# Mainboard.net
KiCad netlist of a schematic drawn in EAGLE
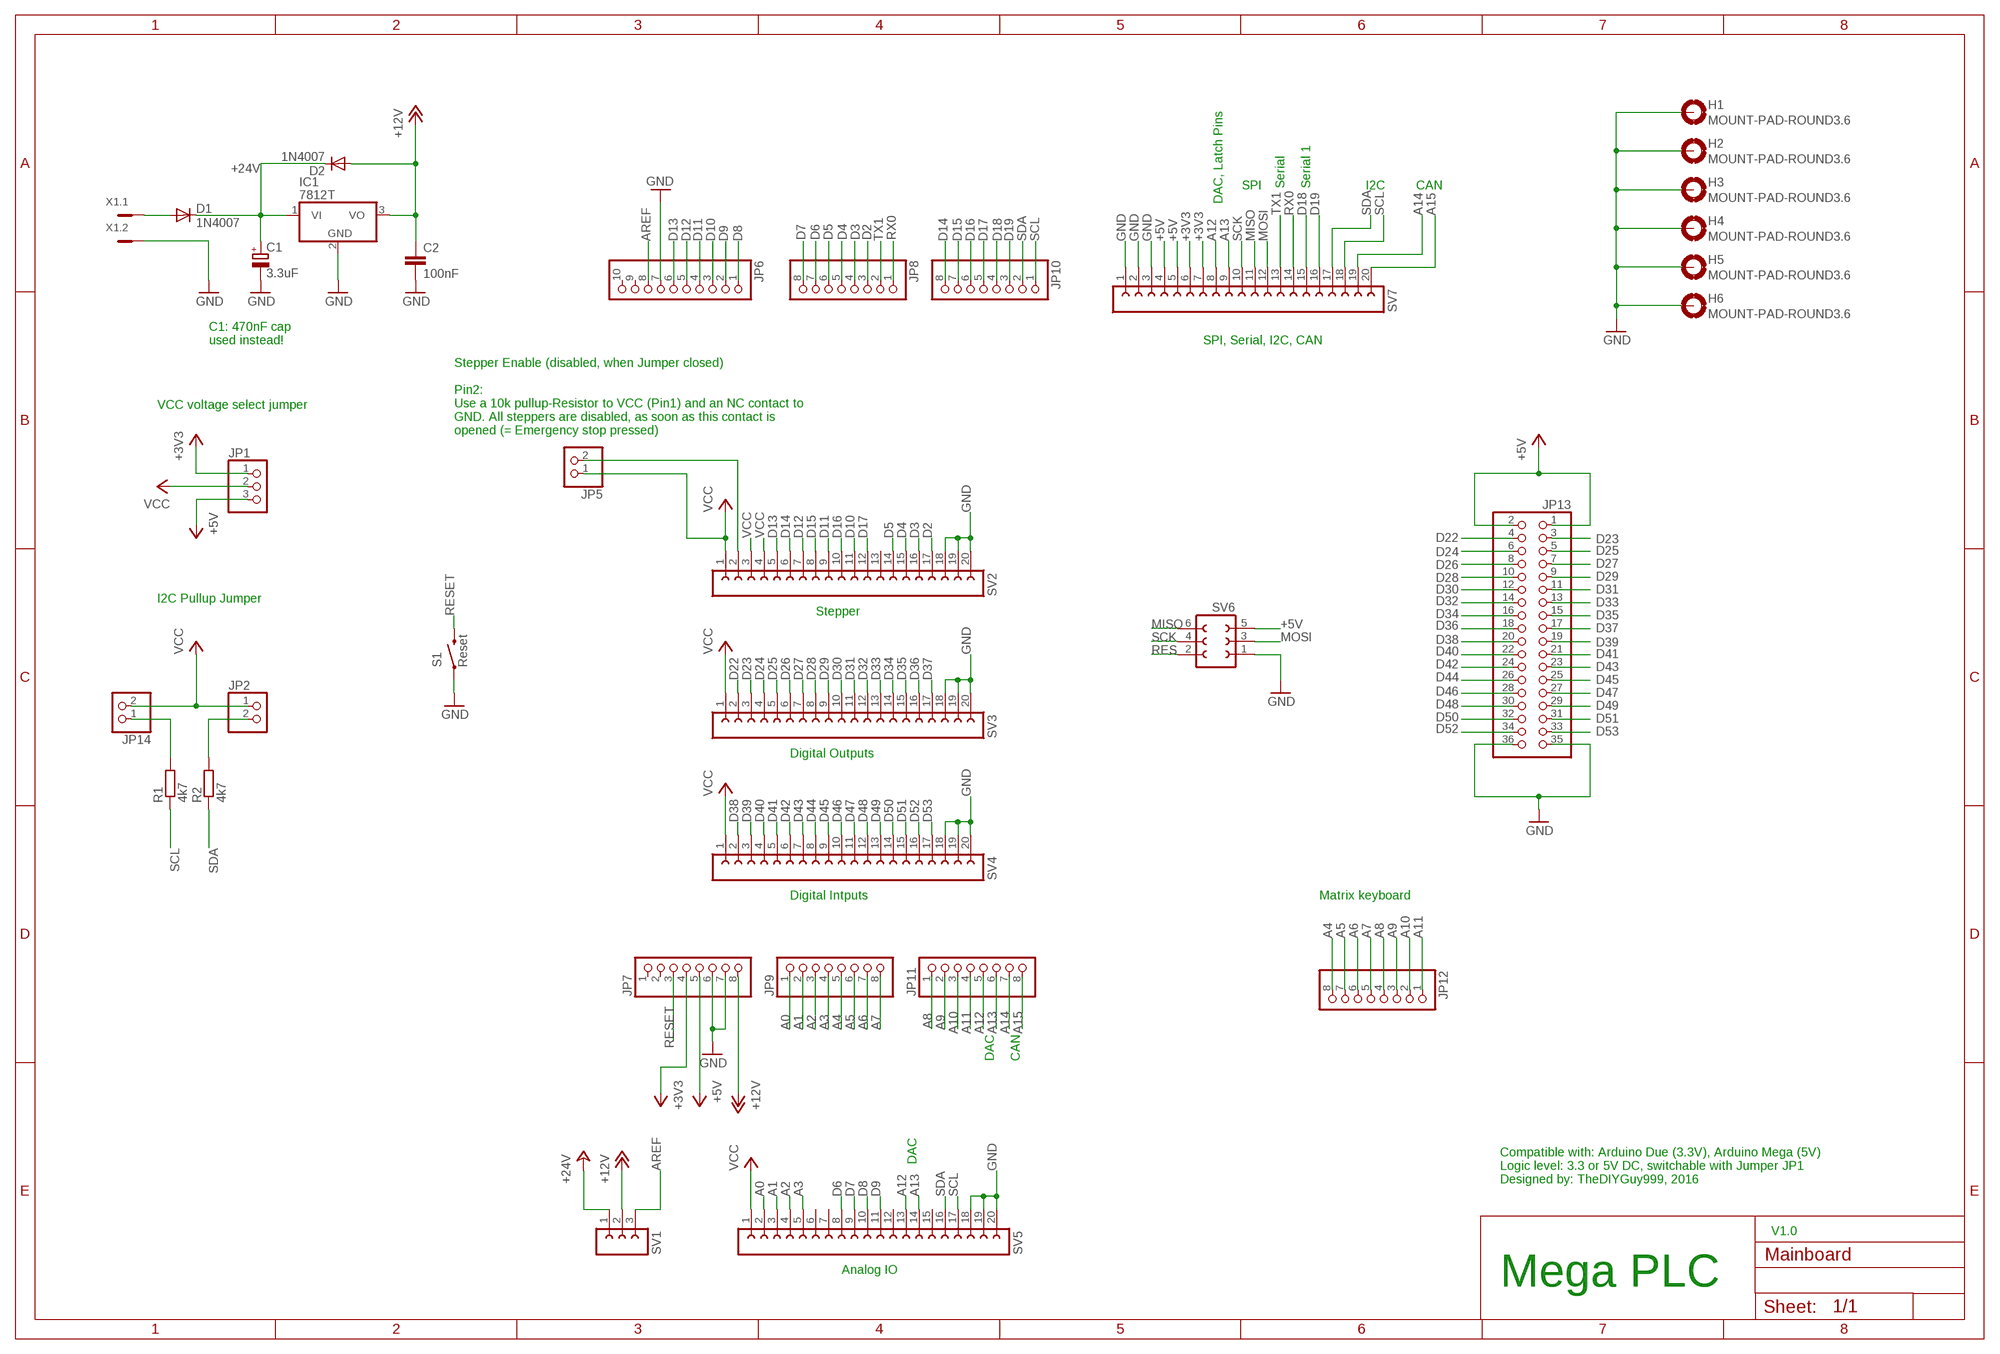
[diagram p0: schematic, sheet 1]

(export (version "E")
  (design (tool "Eeschema 10.0.6"))
  (components
    (comp (ref "C1")
      (value "3.3uF")
      (footprint "eagle-import:B45181A")
      (libsource (lib "eagle-import") (part "CPOL-EUB45181A"))
    )
    (comp (ref "C2")
      (value "100nF")
      (footprint "eagle-import:C025-024X044")
      (libsource (lib "eagle-import") (part "C-EU025-024X044"))
    )
    (comp (ref "D1")
      (value "1N4007")
      (footprint "eagle-import:DO41-10")
      (libsource (lib "eagle-import") (part "1N4004"))
    )
    (comp (ref "D2")
      (value "1N4007")
      (footprint "eagle-import:DO41-10")
      (libsource (lib "eagle-import") (part "1N4004"))
    )
    (comp (ref "H1")
      (value "MOUNT-PAD-ROUND3.6")
      (footprint "eagle-import:3,6-PAD")
      (libsource (lib "eagle-import") (part "MOUNT-PAD-ROUND3.6"))
    )
    (comp (ref "H2")
      (value "MOUNT-PAD-ROUND3.6")
      (footprint "eagle-import:3,6-PAD")
      (libsource (lib "eagle-import") (part "MOUNT-PAD-ROUND3.6"))
    )
    (comp (ref "H3")
      (value "MOUNT-PAD-ROUND3.6")
      (footprint "eagle-import:3,6-PAD")
      (libsource (lib "eagle-import") (part "MOUNT-PAD-ROUND3.6"))
    )
    (comp (ref "H4")
      (value "MOUNT-PAD-ROUND3.6")
      (footprint "eagle-import:3,6-PAD")
      (libsource (lib "eagle-import") (part "MOUNT-PAD-ROUND3.6"))
    )
    (comp (ref "H5")
      (value "MOUNT-PAD-ROUND3.6")
      (footprint "eagle-import:3,6-PAD")
      (libsource (lib "eagle-import") (part "MOUNT-PAD-ROUND3.6"))
    )
    (comp (ref "H6")
      (value "MOUNT-PAD-ROUND3.6")
      (footprint "eagle-import:3,6-PAD")
      (libsource (lib "eagle-import") (part "MOUNT-PAD-ROUND3.6"))
    )
    (comp (ref "IC1")
      (value "7812T")
      (footprint "eagle-import:TO220H")
      (libsource (lib "eagle-import") (part "78T12"))
    )
    (comp (ref "JP1")
      (value "PINHD-1X3")
      (footprint "eagle-import:1X03")
      (libsource (lib "eagle-import") (part "PINHD-1X3"))
    )
    (comp (ref "JP2")
      (value "PINHD-1X2")
      (footprint "eagle-import:1X02")
      (libsource (lib "eagle-import") (part "PINHD-1X2"))
    )
    (comp (ref "JP5")
      (value "PINHD-1X2")
      (footprint "eagle-import:1X02")
      (libsource (lib "eagle-import") (part "PINHD-1X2"))
    )
    (comp (ref "JP6")
      (value "PINHD-1X10")
      (footprint "eagle-import:1X10")
      (libsource (lib "eagle-import") (part "PINHD-1X10"))
    )
    (comp (ref "JP7")
      (value "PINHD-1X8")
      (footprint "eagle-import:1X08")
      (libsource (lib "eagle-import") (part "PINHD-1X8"))
    )
    (comp (ref "JP8")
      (value "PINHD-1X8")
      (footprint "eagle-import:1X08")
      (libsource (lib "eagle-import") (part "PINHD-1X8"))
    )
    (comp (ref "JP9")
      (value "PINHD-1X8")
      (footprint "eagle-import:1X08")
      (libsource (lib "eagle-import") (part "PINHD-1X8"))
    )
    (comp (ref "JP10")
      (value "PINHD-1X8")
      (footprint "eagle-import:1X08")
      (libsource (lib "eagle-import") (part "PINHD-1X8"))
    )
    (comp (ref "JP11")
      (value "PINHD-1X8")
      (footprint "eagle-import:1X08")
      (libsource (lib "eagle-import") (part "PINHD-1X8"))
    )
    (comp (ref "JP12")
      (value "PINHD-1X8")
      (footprint "eagle-import:1X08")
      (libsource (lib "eagle-import") (part "PINHD-1X8"))
    )
    (comp (ref "JP13")
      (value "PINHD-2X18")
      (footprint "eagle-import:2X18")
      (libsource (lib "eagle-import") (part "PINHD-2X18"))
    )
    (comp (ref "JP14")
      (value "PINHD-1X2")
      (footprint "eagle-import:1X02")
      (libsource (lib "eagle-import") (part "PINHD-1X2"))
    )
    (comp (ref "R1")
      (value "4k7")
      (footprint "eagle-import:0207_10")
      (libsource (lib "eagle-import") (part "R-EU_0207/10"))
    )
    (comp (ref "R2")
      (value "4k7")
      (footprint "eagle-import:0207_10")
      (libsource (lib "eagle-import") (part "R-EU_0207/10"))
    )
    (comp (ref "S1")
      (value "Reset")
      (footprint "eagle-import:TACTILE-PTH")
      (libsource (lib "eagle-import") (part "SWITCH-MOMENTARY-2PTH"))
    )
    (comp (ref "SV1")
      (value "FE03-1")
      (footprint "eagle-import:FE03-1")
      (libsource (lib "eagle-import") (part "FE03-1"))
    )
    (comp (ref "SV2")
      (value "FE20-1")
      (footprint "eagle-import:FE20")
      (libsource (lib "eagle-import") (part "FE20-1"))
    )
    (comp (ref "SV3")
      (value "FE20-1")
      (footprint "eagle-import:FE20")
      (libsource (lib "eagle-import") (part "FE20-1"))
    )
    (comp (ref "SV4")
      (value "FE20-1")
      (footprint "eagle-import:FE20")
      (libsource (lib "eagle-import") (part "FE20-1"))
    )
    (comp (ref "SV5")
      (value "FE20-1")
      (footprint "eagle-import:FE20")
      (libsource (lib "eagle-import") (part "FE20-1"))
    )
    (comp (ref "SV6")
      (value "FE03-2")
      (footprint "eagle-import:FE03-2")
      (libsource (lib "eagle-import") (part "FE03-2"))
    )
    (comp (ref "SV7")
      (value "FE20-1")
      (footprint "eagle-import:FE20")
      (libsource (lib "eagle-import") (part "FE20-1"))
    )
    (comp (ref "X1")
      (value "MC2")
      (footprint "eagle-import:MC2")
      (libsource (lib "eagle-import") (part "MC2"))
    )
  )
  (nets
    (net (code "1") (name "+3V3") (class "Default")
      (node (ref "JP1") (pin "1") (pinfunction "1_1") (pintype "passive"))
      (node (ref "JP7") (pin "4") (pinfunction "4_4") (pintype "passive"))
      (node (ref "SV7") (pin "6") (pinfunction "6_6") (pintype "passive"))
      (node (ref "SV7") (pin "7") (pinfunction "7_7") (pintype "passive"))
    )
    (net (code "2") (name "+5V") (class "Default")
      (node (ref "JP1") (pin "3") (pinfunction "3_3") (pintype "passive"))
      (node (ref "JP13") (pin "1") (pinfunction "1_1") (pintype "passive"))
      (node (ref "JP13") (pin "2") (pinfunction "2_2") (pintype "passive"))
      (node (ref "JP7") (pin "5") (pinfunction "5_5") (pintype "passive"))
      (node (ref "SV6") (pin "5") (pinfunction "5_5") (pintype "passive"))
      (node (ref "SV7") (pin "4") (pinfunction "4_4") (pintype "passive"))
      (node (ref "SV7") (pin "5") (pinfunction "5_5") (pintype "passive"))
    )
    (net (code "3") (name "+12V") (class "Default")
      (node (ref "C2") (pin "1") (pinfunction "1_1") (pintype "passive"))
      (node (ref "D2") (pin "A") (pinfunction "A_A") (pintype "passive"))
      (node (ref "IC1") (pin "3") (pinfunction "VO_3") (pintype "passive"))
      (node (ref "JP7") (pin "8") (pinfunction "8_8") (pintype "passive"))
      (node (ref "SV1") (pin "2") (pinfunction "2_2") (pintype "passive"))
    )
    (net (code "4") (name "+24V") (class "Default")
      (node (ref "C1") (pin "+") (pinfunction "+_+") (pintype "passive"))
      (node (ref "D1") (pin "C") (pinfunction "C_C") (pintype "passive"))
      (node (ref "D2") (pin "C") (pinfunction "C_C") (pintype "passive"))
      (node (ref "IC1") (pin "1") (pinfunction "VI_1") (pintype "input"))
      (node (ref "SV1") (pin "1") (pinfunction "1_1") (pintype "passive"))
    )
    (net (code "5") (name "/A0") (class "Default")
      (node (ref "JP9") (pin "1") (pinfunction "1_1") (pintype "passive"))
      (node (ref "SV5") (pin "2") (pinfunction "2_2") (pintype "passive"))
    )
    (net (code "6") (name "/A1") (class "Default")
      (node (ref "JP9") (pin "2") (pinfunction "2_2") (pintype "passive"))
      (node (ref "SV5") (pin "3") (pinfunction "3_3") (pintype "passive"))
    )
    (net (code "7") (name "/A2") (class "Default")
      (node (ref "JP9") (pin "3") (pinfunction "3_3") (pintype "passive"))
      (node (ref "SV5") (pin "4") (pinfunction "4_4") (pintype "passive"))
    )
    (net (code "8") (name "/A3") (class "Default")
      (node (ref "JP9") (pin "4") (pinfunction "4_4") (pintype "passive"))
      (node (ref "SV5") (pin "5") (pinfunction "5_5") (pintype "passive"))
    )
    (net (code "9") (name "/A4") (class "Default")
      (node (ref "JP12") (pin "8") (pinfunction "8_8") (pintype "passive"))
      (node (ref "JP9") (pin "5") (pinfunction "5_5") (pintype "passive"))
    )
    (net (code "10") (name "/A5") (class "Default")
      (node (ref "JP12") (pin "7") (pinfunction "7_7") (pintype "passive"))
      (node (ref "JP9") (pin "6") (pinfunction "6_6") (pintype "passive"))
    )
    (net (code "11") (name "/A6") (class "Default")
      (node (ref "JP12") (pin "6") (pinfunction "6_6") (pintype "passive"))
      (node (ref "JP9") (pin "7") (pinfunction "7_7") (pintype "passive"))
    )
    (net (code "12") (name "/A7") (class "Default")
      (node (ref "JP12") (pin "5") (pinfunction "5_5") (pintype "passive"))
      (node (ref "JP9") (pin "8") (pinfunction "8_8") (pintype "passive"))
    )
    (net (code "13") (name "/A8") (class "Default")
      (node (ref "JP11") (pin "1") (pinfunction "1_1") (pintype "passive"))
      (node (ref "JP12") (pin "4") (pinfunction "4_4") (pintype "passive"))
    )
    (net (code "14") (name "/A9") (class "Default")
      (node (ref "JP11") (pin "2") (pinfunction "2_2") (pintype "passive"))
      (node (ref "JP12") (pin "3") (pinfunction "3_3") (pintype "passive"))
    )
    (net (code "15") (name "/A10") (class "Default")
      (node (ref "JP11") (pin "3") (pinfunction "3_3") (pintype "passive"))
      (node (ref "JP12") (pin "2") (pinfunction "2_2") (pintype "passive"))
    )
    (net (code "16") (name "/A11") (class "Default")
      (node (ref "JP11") (pin "4") (pinfunction "4_4") (pintype "passive"))
      (node (ref "JP12") (pin "1") (pinfunction "1_1") (pintype "passive"))
    )
    (net (code "17") (name "/A12") (class "Default")
      (node (ref "JP11") (pin "5") (pinfunction "5_5") (pintype "passive"))
      (node (ref "SV5") (pin "13") (pinfunction "13_13") (pintype "passive"))
      (node (ref "SV7") (pin "8") (pinfunction "8_8") (pintype "passive"))
    )
    (net (code "18") (name "/A13") (class "Default")
      (node (ref "JP11") (pin "6") (pinfunction "6_6") (pintype "passive"))
      (node (ref "SV5") (pin "14") (pinfunction "14_14") (pintype "passive"))
      (node (ref "SV7") (pin "9") (pinfunction "9_9") (pintype "passive"))
    )
    (net (code "19") (name "/A14") (class "Default")
      (node (ref "JP11") (pin "7") (pinfunction "7_7") (pintype "passive"))
      (node (ref "SV7") (pin "19") (pinfunction "19_19") (pintype "passive"))
    )
    (net (code "20") (name "/A15") (class "Default")
      (node (ref "JP11") (pin "8") (pinfunction "8_8") (pintype "passive"))
      (node (ref "SV7") (pin "20") (pinfunction "20_20") (pintype "passive"))
    )
    (net (code "21") (name "/AREF") (class "Default")
      (node (ref "JP6") (pin "8") (pinfunction "8_8") (pintype "passive"))
      (node (ref "SV1") (pin "3") (pinfunction "3_3") (pintype "passive"))
    )
    (net (code "22") (name "/D2") (class "Default")
      (node (ref "JP8") (pin "3") (pinfunction "3_3") (pintype "passive"))
      (node (ref "SV2") (pin "17") (pinfunction "17_17") (pintype "passive"))
    )
    (net (code "23") (name "/D3") (class "Default")
      (node (ref "JP8") (pin "4") (pinfunction "4_4") (pintype "passive"))
      (node (ref "SV2") (pin "16") (pinfunction "16_16") (pintype "passive"))
    )
    (net (code "24") (name "/D4") (class "Default")
      (node (ref "JP8") (pin "5") (pinfunction "5_5") (pintype "passive"))
      (node (ref "SV2") (pin "15") (pinfunction "15_15") (pintype "passive"))
    )
    (net (code "25") (name "/D5") (class "Default")
      (node (ref "JP8") (pin "6") (pinfunction "6_6") (pintype "passive"))
      (node (ref "SV2") (pin "14") (pinfunction "14_14") (pintype "passive"))
    )
    (net (code "26") (name "/D6") (class "Default")
      (node (ref "JP8") (pin "7") (pinfunction "7_7") (pintype "passive"))
      (node (ref "SV5") (pin "8") (pinfunction "8_8") (pintype "passive"))
    )
    (net (code "27") (name "/D7") (class "Default")
      (node (ref "JP8") (pin "8") (pinfunction "8_8") (pintype "passive"))
      (node (ref "SV5") (pin "9") (pinfunction "9_9") (pintype "passive"))
    )
    (net (code "28") (name "/D8") (class "Default")
      (node (ref "JP6") (pin "1") (pinfunction "1_1") (pintype "passive"))
      (node (ref "SV5") (pin "10") (pinfunction "10_10") (pintype "passive"))
    )
    (net (code "29") (name "/D9") (class "Default")
      (node (ref "JP6") (pin "2") (pinfunction "2_2") (pintype "passive"))
      (node (ref "SV5") (pin "11") (pinfunction "11_11") (pintype "passive"))
    )
    (net (code "30") (name "/D10") (class "Default")
      (node (ref "JP6") (pin "3") (pinfunction "3_3") (pintype "passive"))
      (node (ref "SV2") (pin "11") (pinfunction "11_11") (pintype "passive"))
    )
    (net (code "31") (name "/D11") (class "Default")
      (node (ref "JP6") (pin "4") (pinfunction "4_4") (pintype "passive"))
      (node (ref "SV2") (pin "9") (pinfunction "9_9") (pintype "passive"))
    )
    (net (code "32") (name "/D12") (class "Default")
      (node (ref "JP6") (pin "5") (pinfunction "5_5") (pintype "passive"))
      (node (ref "SV2") (pin "7") (pinfunction "7_7") (pintype "passive"))
    )
    (net (code "33") (name "/D13") (class "Default")
      (node (ref "JP6") (pin "6") (pinfunction "6_6") (pintype "passive"))
      (node (ref "SV2") (pin "5") (pinfunction "5_5") (pintype "passive"))
    )
    (net (code "34") (name "/D14") (class "Default")
      (node (ref "JP10") (pin "8") (pinfunction "8_8") (pintype "passive"))
      (node (ref "SV2") (pin "6") (pinfunction "6_6") (pintype "passive"))
    )
    (net (code "35") (name "/D15") (class "Default")
      (node (ref "JP10") (pin "7") (pinfunction "7_7") (pintype "passive"))
      (node (ref "SV2") (pin "8") (pinfunction "8_8") (pintype "passive"))
    )
    (net (code "36") (name "/D16") (class "Default")
      (node (ref "JP10") (pin "6") (pinfunction "6_6") (pintype "passive"))
      (node (ref "SV2") (pin "10") (pinfunction "10_10") (pintype "passive"))
    )
    (net (code "37") (name "/D17") (class "Default")
      (node (ref "JP10") (pin "5") (pinfunction "5_5") (pintype "passive"))
      (node (ref "SV2") (pin "12") (pinfunction "12_12") (pintype "passive"))
    )
    (net (code "38") (name "/D18") (class "Default")
      (node (ref "JP10") (pin "4") (pinfunction "4_4") (pintype "passive"))
      (node (ref "SV7") (pin "15") (pinfunction "15_15") (pintype "passive"))
    )
    (net (code "39") (name "/D19") (class "Default")
      (node (ref "JP10") (pin "3") (pinfunction "3_3") (pintype "passive"))
      (node (ref "SV7") (pin "16") (pinfunction "16_16") (pintype "passive"))
    )
    (net (code "40") (name "/D22") (class "Default")
      (node (ref "JP13") (pin "4") (pinfunction "4_4") (pintype "passive"))
      (node (ref "SV3") (pin "2") (pinfunction "2_2") (pintype "passive"))
    )
    (net (code "41") (name "/D23") (class "Default")
      (node (ref "JP13") (pin "3") (pinfunction "3_3") (pintype "passive"))
      (node (ref "SV3") (pin "3") (pinfunction "3_3") (pintype "passive"))
    )
    (net (code "42") (name "/D24") (class "Default")
      (node (ref "JP13") (pin "6") (pinfunction "6_6") (pintype "passive"))
      (node (ref "SV3") (pin "4") (pinfunction "4_4") (pintype "passive"))
    )
    (net (code "43") (name "/D25") (class "Default")
      (node (ref "JP13") (pin "5") (pinfunction "5_5") (pintype "passive"))
      (node (ref "SV3") (pin "5") (pinfunction "5_5") (pintype "passive"))
    )
    (net (code "44") (name "/D26") (class "Default")
      (node (ref "JP13") (pin "8") (pinfunction "8_8") (pintype "passive"))
      (node (ref "SV3") (pin "6") (pinfunction "6_6") (pintype "passive"))
    )
    (net (code "45") (name "/D27") (class "Default")
      (node (ref "JP13") (pin "7") (pinfunction "7_7") (pintype "passive"))
      (node (ref "SV3") (pin "7") (pinfunction "7_7") (pintype "passive"))
    )
    (net (code "46") (name "/D28") (class "Default")
      (node (ref "JP13") (pin "10") (pinfunction "10_10") (pintype "passive"))
      (node (ref "SV3") (pin "8") (pinfunction "8_8") (pintype "passive"))
    )
    (net (code "47") (name "/D29") (class "Default")
      (node (ref "JP13") (pin "9") (pinfunction "9_9") (pintype "passive"))
      (node (ref "SV3") (pin "9") (pinfunction "9_9") (pintype "passive"))
    )
    (net (code "48") (name "/D30") (class "Default")
      (node (ref "JP13") (pin "12") (pinfunction "12_12") (pintype "passive"))
      (node (ref "SV3") (pin "10") (pinfunction "10_10") (pintype "passive"))
    )
    (net (code "49") (name "/D31") (class "Default")
      (node (ref "JP13") (pin "11") (pinfunction "11_11") (pintype "passive"))
      (node (ref "SV3") (pin "11") (pinfunction "11_11") (pintype "passive"))
    )
    (net (code "50") (name "/D32") (class "Default")
      (node (ref "JP13") (pin "14") (pinfunction "14_14") (pintype "passive"))
      (node (ref "SV3") (pin "12") (pinfunction "12_12") (pintype "passive"))
    )
    (net (code "51") (name "/D33") (class "Default")
      (node (ref "JP13") (pin "13") (pinfunction "13_13") (pintype "passive"))
      (node (ref "SV3") (pin "13") (pinfunction "13_13") (pintype "passive"))
    )
    (net (code "52") (name "/D34") (class "Default")
      (node (ref "JP13") (pin "16") (pinfunction "16_16") (pintype "passive"))
      (node (ref "SV3") (pin "14") (pinfunction "14_14") (pintype "passive"))
    )
    (net (code "53") (name "/D35") (class "Default")
      (node (ref "JP13") (pin "15") (pinfunction "15_15") (pintype "passive"))
      (node (ref "SV3") (pin "15") (pinfunction "15_15") (pintype "passive"))
    )
    (net (code "54") (name "/D36") (class "Default")
      (node (ref "JP13") (pin "18") (pinfunction "18_18") (pintype "passive"))
      (node (ref "SV3") (pin "16") (pinfunction "16_16") (pintype "passive"))
    )
    (net (code "55") (name "/D37") (class "Default")
      (node (ref "JP13") (pin "17") (pinfunction "17_17") (pintype "passive"))
      (node (ref "SV3") (pin "17") (pinfunction "17_17") (pintype "passive"))
    )
    (net (code "56") (name "/D38") (class "Default")
      (node (ref "JP13") (pin "20") (pinfunction "20_20") (pintype "passive"))
      (node (ref "SV4") (pin "2") (pinfunction "2_2") (pintype "passive"))
    )
    (net (code "57") (name "/D39") (class "Default")
      (node (ref "JP13") (pin "19") (pinfunction "19_19") (pintype "passive"))
      (node (ref "SV4") (pin "3") (pinfunction "3_3") (pintype "passive"))
    )
    (net (code "58") (name "/D40") (class "Default")
      (node (ref "JP13") (pin "22") (pinfunction "22_22") (pintype "passive"))
      (node (ref "SV4") (pin "4") (pinfunction "4_4") (pintype "passive"))
    )
    (net (code "59") (name "/D41") (class "Default")
      (node (ref "JP13") (pin "21") (pinfunction "21_21") (pintype "passive"))
      (node (ref "SV4") (pin "5") (pinfunction "5_5") (pintype "passive"))
    )
    (net (code "60") (name "/D42") (class "Default")
      (node (ref "JP13") (pin "24") (pinfunction "24_24") (pintype "passive"))
      (node (ref "SV4") (pin "6") (pinfunction "6_6") (pintype "passive"))
    )
    (net (code "61") (name "/D43") (class "Default")
      (node (ref "JP13") (pin "23") (pinfunction "23_23") (pintype "passive"))
      (node (ref "SV4") (pin "7") (pinfunction "7_7") (pintype "passive"))
    )
    (net (code "62") (name "/D44") (class "Default")
      (node (ref "JP13") (pin "26") (pinfunction "26_26") (pintype "passive"))
      (node (ref "SV4") (pin "8") (pinfunction "8_8") (pintype "passive"))
    )
    (net (code "63") (name "/D45") (class "Default")
      (node (ref "JP13") (pin "25") (pinfunction "25_25") (pintype "passive"))
      (node (ref "SV4") (pin "9") (pinfunction "9_9") (pintype "passive"))
    )
    (net (code "64") (name "/D46") (class "Default")
      (node (ref "JP13") (pin "28") (pinfunction "28_28") (pintype "passive"))
      (node (ref "SV4") (pin "10") (pinfunction "10_10") (pintype "passive"))
    )
    (net (code "65") (name "/D47") (class "Default")
      (node (ref "JP13") (pin "27") (pinfunction "27_27") (pintype "passive"))
      (node (ref "SV4") (pin "11") (pinfunction "11_11") (pintype "passive"))
    )
    (net (code "66") (name "/D48") (class "Default")
      (node (ref "JP13") (pin "30") (pinfunction "30_30") (pintype "passive"))
      (node (ref "SV4") (pin "12") (pinfunction "12_12") (pintype "passive"))
    )
    (net (code "67") (name "/D49") (class "Default")
      (node (ref "JP13") (pin "29") (pinfunction "29_29") (pintype "passive"))
      (node (ref "SV4") (pin "13") (pinfunction "13_13") (pintype "passive"))
    )
    (net (code "68") (name "/D50") (class "Default")
      (node (ref "JP13") (pin "32") (pinfunction "32_32") (pintype "passive"))
      (node (ref "SV4") (pin "14") (pinfunction "14_14") (pintype "passive"))
    )
    (net (code "69") (name "/D51") (class "Default")
      (node (ref "JP13") (pin "31") (pinfunction "31_31") (pintype "passive"))
      (node (ref "SV4") (pin "15") (pinfunction "15_15") (pintype "passive"))
    )
    (net (code "70") (name "/D52") (class "Default")
      (node (ref "JP13") (pin "34") (pinfunction "34_34") (pintype "passive"))
      (node (ref "SV4") (pin "16") (pinfunction "16_16") (pintype "passive"))
    )
    (net (code "71") (name "/D53") (class "Default")
      (node (ref "JP13") (pin "33") (pinfunction "33_33") (pintype "passive"))
      (node (ref "SV4") (pin "17") (pinfunction "17_17") (pintype "passive"))
    )
    (net (code "72") (name "/MISO") (class "Default")
      (node (ref "SV6") (pin "6") (pinfunction "6_6") (pintype "passive"))
      (node (ref "SV7") (pin "11") (pinfunction "11_11") (pintype "passive"))
    )
    (net (code "73") (name "/MOSI") (class "Default")
      (node (ref "SV6") (pin "3") (pinfunction "3_3") (pintype "passive"))
      (node (ref "SV7") (pin "12") (pinfunction "12_12") (pintype "passive"))
    )
    (net (code "74") (name "/RES") (class "Default")
      (node (ref "SV6") (pin "2") (pinfunction "2_2") (pintype "passive"))
    )
    (net (code "75") (name "/RESET") (class "Default")
      (node (ref "JP7") (pin "3") (pinfunction "3_3") (pintype "passive"))
      (node (ref "S1") (pin "3") (pinfunction "2_3") (pintype "passive"))
    )
    (net (code "76") (name "/RX0") (class "Default")
      (node (ref "JP8") (pin "1") (pinfunction "1_1") (pintype "passive"))
      (node (ref "SV7") (pin "14") (pinfunction "14_14") (pintype "passive"))
    )
    (net (code "77") (name "/SCK") (class "Default")
      (node (ref "SV6") (pin "4") (pinfunction "4_4") (pintype "passive"))
      (node (ref "SV7") (pin "10") (pinfunction "10_10") (pintype "passive"))
    )
    (net (code "78") (name "/SCL") (class "Default")
      (node (ref "JP10") (pin "1") (pinfunction "1_1") (pintype "passive"))
      (node (ref "R1") (pin "1") (pinfunction "1_1") (pintype "passive"))
      (node (ref "SV5") (pin "17") (pinfunction "17_17") (pintype "passive"))
      (node (ref "SV7") (pin "18") (pinfunction "18_18") (pintype "passive"))
    )
    (net (code "79") (name "/SDA") (class "Default")
      (node (ref "JP10") (pin "2") (pinfunction "2_2") (pintype "passive"))
      (node (ref "R2") (pin "1") (pinfunction "1_1") (pintype "passive"))
      (node (ref "SV5") (pin "16") (pinfunction "16_16") (pintype "passive"))
      (node (ref "SV7") (pin "17") (pinfunction "17_17") (pintype "passive"))
    )
    (net (code "80") (name "/TX1") (class "Default")
      (node (ref "JP8") (pin "2") (pinfunction "2_2") (pintype "passive"))
      (node (ref "SV7") (pin "13") (pinfunction "13_13") (pintype "passive"))
    )
    (net (code "81") (name "GND") (class "Default")
      (node (ref "C1") (pin "-") (pinfunction "-_-") (pintype "passive"))
      (node (ref "C2") (pin "2") (pinfunction "2_2") (pintype "passive"))
      (node (ref "H1") (pin "B3,6") (pinfunction "MOUNT_B3,6") (pintype "passive"))
      (node (ref "H2") (pin "B3,6") (pinfunction "MOUNT_B3,6") (pintype "passive"))
      (node (ref "H3") (pin "B3,6") (pinfunction "MOUNT_B3,6") (pintype "passive"))
      (node (ref "H4") (pin "B3,6") (pinfunction "MOUNT_B3,6") (pintype "passive"))
      (node (ref "H5") (pin "B3,6") (pinfunction "MOUNT_B3,6") (pintype "passive"))
      (node (ref "H6") (pin "B3,6") (pinfunction "MOUNT_B3,6") (pintype "passive"))
      (node (ref "IC1") (pin "2") (pinfunction "GND_2") (pintype "passive"))
      (node (ref "JP13") (pin "35") (pinfunction "35_35") (pintype "passive"))
      (node (ref "JP13") (pin "36") (pinfunction "36_36") (pintype "passive"))
      (node (ref "JP6") (pin "7") (pinfunction "7_7") (pintype "passive"))
      (node (ref "JP7") (pin "6") (pinfunction "6_6") (pintype "passive"))
      (node (ref "JP7") (pin "7") (pinfunction "7_7") (pintype "passive"))
      (node (ref "S1") (pin "1") (pinfunction "1_1") (pintype "passive"))
      (node (ref "SV2") (pin "18") (pinfunction "18_18") (pintype "passive"))
      (node (ref "SV2") (pin "19") (pinfunction "19_19") (pintype "passive"))
      (node (ref "SV2") (pin "20") (pinfunction "20_20") (pintype "passive"))
      (node (ref "SV3") (pin "18") (pinfunction "18_18") (pintype "passive"))
      (node (ref "SV3") (pin "19") (pinfunction "19_19") (pintype "passive"))
      (node (ref "SV3") (pin "20") (pinfunction "20_20") (pintype "passive"))
      (node (ref "SV4") (pin "18") (pinfunction "18_18") (pintype "passive"))
      (node (ref "SV4") (pin "19") (pinfunction "19_19") (pintype "passive"))
      (node (ref "SV4") (pin "20") (pinfunction "20_20") (pintype "passive"))
      (node (ref "SV5") (pin "18") (pinfunction "18_18") (pintype "passive"))
      (node (ref "SV5") (pin "19") (pinfunction "19_19") (pintype "passive"))
      (node (ref "SV5") (pin "20") (pinfunction "20_20") (pintype "passive"))
      (node (ref "SV6") (pin "1") (pinfunction "1_1") (pintype "passive"))
      (node (ref "SV7") (pin "1") (pinfunction "1_1") (pintype "passive"))
      (node (ref "SV7") (pin "2") (pinfunction "2_2") (pintype "passive"))
      (node (ref "SV7") (pin "3") (pinfunction "3_3") (pintype "passive"))
      (node (ref "X1") (pin "2") (pinfunction "SK_2") (pintype "passive"))
    )
    (net (code "82") (name "Net-(JP2-Pad2)") (class "Default")
      (node (ref "JP2") (pin "2") (pinfunction "2_2") (pintype "passive"))
      (node (ref "R2") (pin "2") (pinfunction "2_2") (pintype "passive"))
    )
    (net (code "83") (name "Net-(JP5-Pad2)") (class "Default")
      (node (ref "JP5") (pin "2") (pinfunction "2_2") (pintype "passive"))
      (node (ref "SV2") (pin "2") (pinfunction "2_2") (pintype "passive"))
    )
    (net (code "84") (name "Net-(JP14-Pad1)") (class "Default")
      (node (ref "JP14") (pin "1") (pinfunction "1_1") (pintype "passive"))
      (node (ref "R1") (pin "2") (pinfunction "2_2") (pintype "passive"))
    )
    (net (code "85") (name "Net-(X1A-SK)") (class "Default")
      (node (ref "D1") (pin "A") (pinfunction "A_A") (pintype "passive"))
      (node (ref "X1") (pin "1") (pinfunction "SK_1") (pintype "passive"))
    )
    (net (code "86") (name "VCC") (class "Default")
      (node (ref "JP1") (pin "2") (pinfunction "2_2") (pintype "passive"))
      (node (ref "JP14") (pin "2") (pinfunction "2_2") (pintype "passive"))
      (node (ref "JP2") (pin "1") (pinfunction "1_1") (pintype "passive"))
      (node (ref "JP5") (pin "1") (pinfunction "1_1") (pintype "passive"))
      (node (ref "SV2") (pin "1") (pinfunction "1_1") (pintype "passive"))
      (node (ref "SV2") (pin "3") (pinfunction "3_3") (pintype "passive"))
      (node (ref "SV2") (pin "4") (pinfunction "4_4") (pintype "passive"))
      (node (ref "SV3") (pin "1") (pinfunction "1_1") (pintype "passive"))
      (node (ref "SV4") (pin "1") (pinfunction "1_1") (pintype "passive"))
      (node (ref "SV5") (pin "1") (pinfunction "1_1") (pintype "passive"))
    )
    (net (code "87") (name "unconnected-(JP6-Pad9)") (class "Default")
      (node (ref "JP6") (pin "9") (pinfunction "9_9") (pintype "passive"))
    )
    (net (code "88") (name "unconnected-(JP6-Pad10)") (class "Default")
      (node (ref "JP6") (pin "10") (pinfunction "10_10") (pintype "passive"))
    )
    (net (code "89") (name "unconnected-(JP7-Pad1)") (class "Default")
      (node (ref "JP7") (pin "1") (pinfunction "1_1") (pintype "passive"))
    )
    (net (code "90") (name "unconnected-(JP7-Pad2)") (class "Default")
      (node (ref "JP7") (pin "2") (pinfunction "2_2") (pintype "passive"))
    )
    (net (code "91") (name "unconnected-(SV2-Pad13)") (class "Default")
      (node (ref "SV2") (pin "13") (pinfunction "13_13") (pintype "passive"))
    )
    (net (code "92") (name "unconnected-(SV5-Pad6)") (class "Default")
      (node (ref "SV5") (pin "6") (pinfunction "6_6") (pintype "passive"))
    )
    (net (code "93") (name "unconnected-(SV5-Pad7)") (class "Default")
      (node (ref "SV5") (pin "7") (pinfunction "7_7") (pintype "passive"))
    )
    (net (code "94") (name "unconnected-(SV5-Pad12)") (class "Default")
      (node (ref "SV5") (pin "12") (pinfunction "12_12") (pintype "passive"))
    )
    (net (code "95") (name "unconnected-(SV5-Pad15)") (class "Default")
      (node (ref "SV5") (pin "15") (pinfunction "15_15") (pintype "passive"))
    )
  )
)
